# charge_battery.net
KiCad netlist of a schematic drawn in Altium Designer
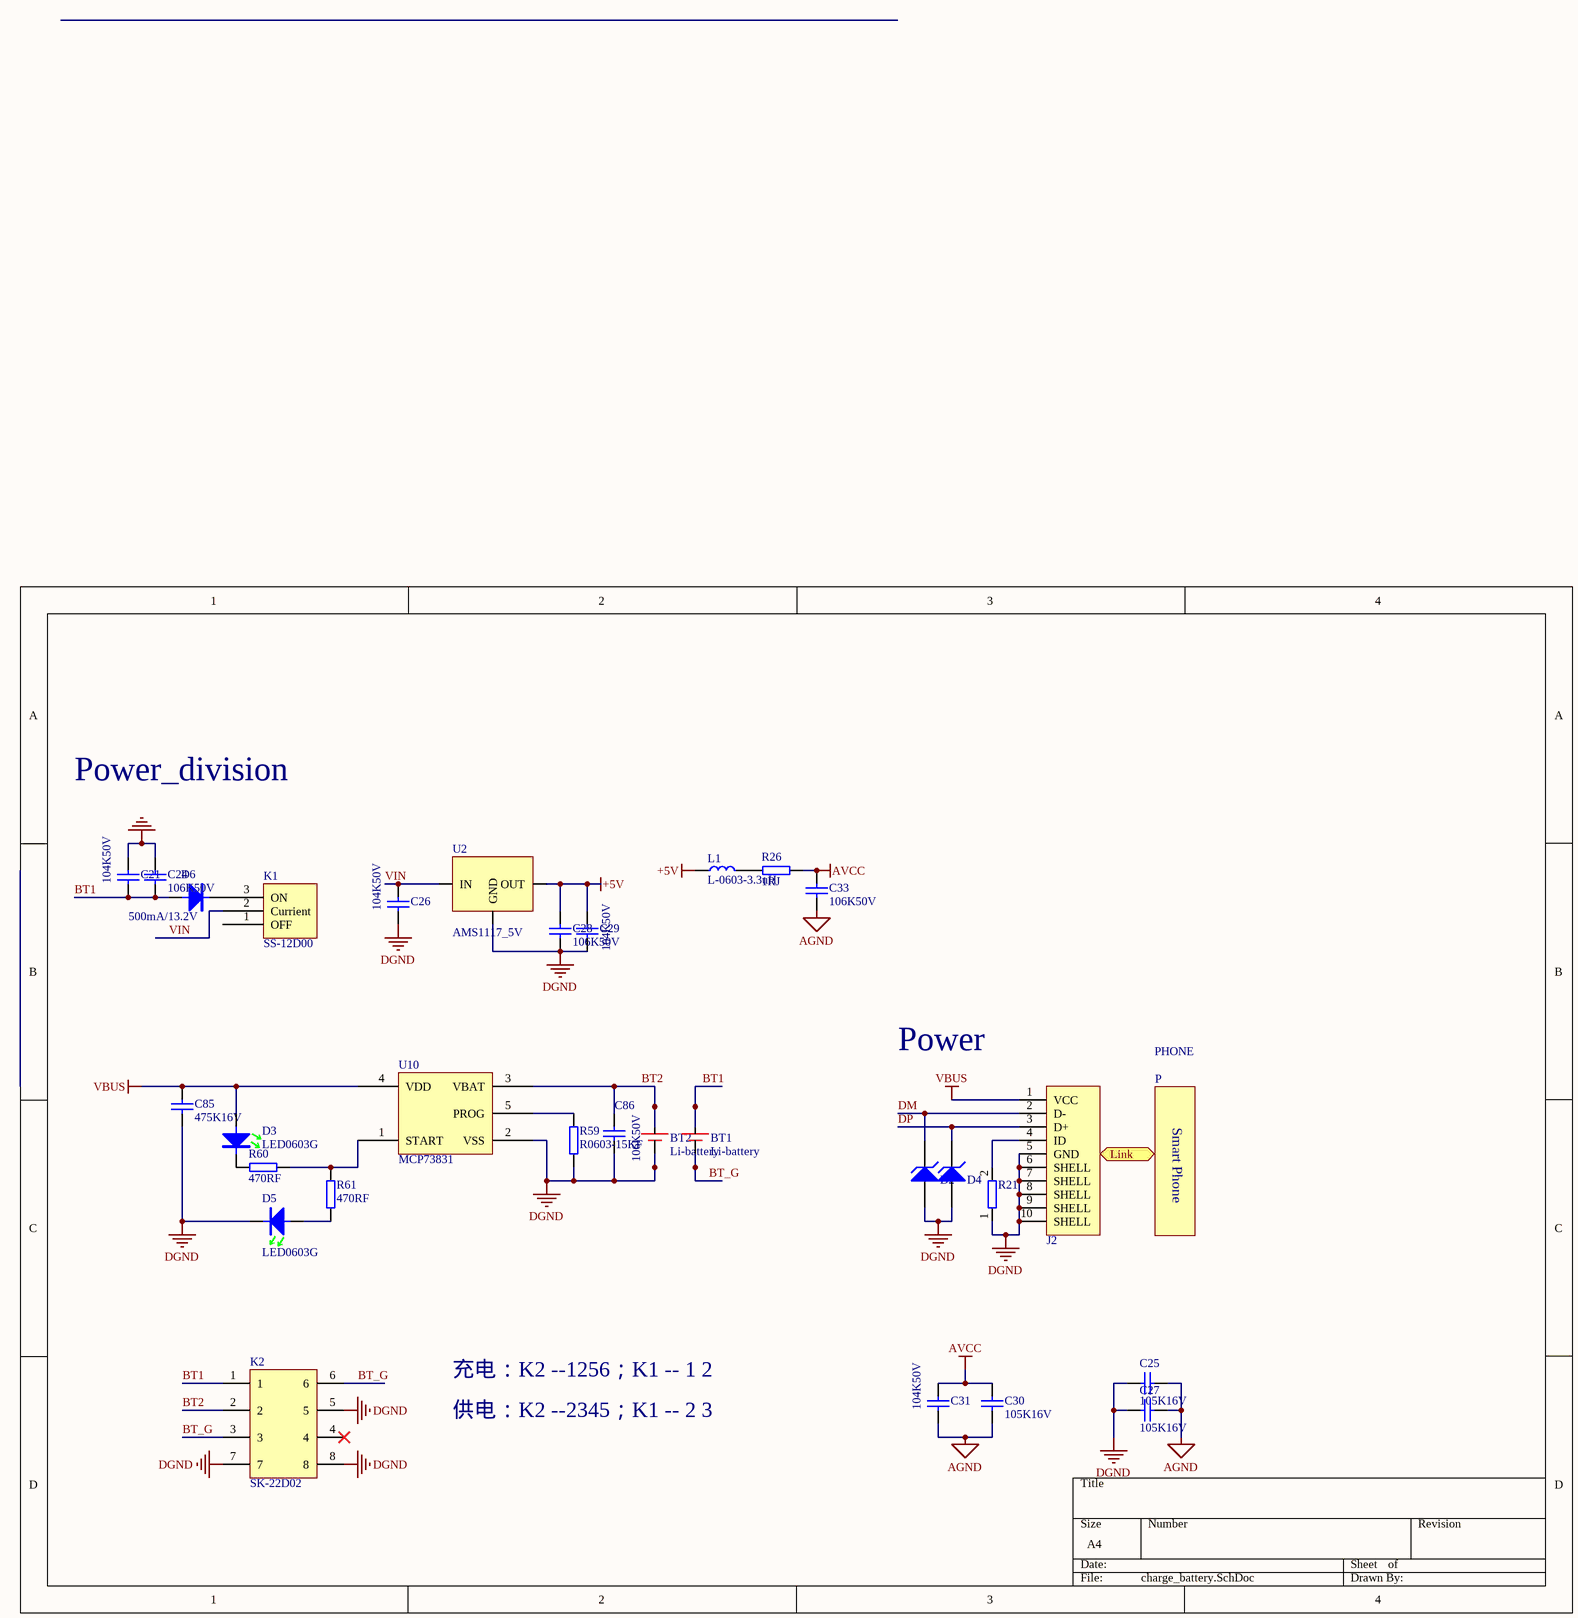
[diagram p0: charge_battery.SchDoc]

(export (version "E")
  (design (tool "Eeschema 10.0.6"))
  (components
    (comp (ref "BT1")
      (value "Li-battery")
      (footprint "LIR2032")
      (description "纽扣电池LIR2023")
      (libsource (lib "Others") (part "Li-batttery"))
    )
    (comp (ref "BT2")
      (value "Li-battery")
      (footprint "LIR2032")
      (description "纽扣电池LIR2023")
      (libsource (lib "Others") (part "Li-batttery"))
    )
    (comp (ref "C21")
      (value "104K50V")
      (footprint "C0603")
      (description "贴片电容-陶瓷")
      (libsource (lib "Capacitor") (part "C0603X7R-104K50V"))
    )
    (comp (ref "C24")
      (value "106K50V")
      (footprint "C0603")
      (description "贴片电容-陶瓷")
      (libsource (lib "Capacitor") (part "C0603X7R-106K50V"))
    )
    (comp (ref "C25")
      (value "105K16V")
      (footprint "C0603")
      (description "贴片电容-陶瓷")
      (libsource (lib "Capacitor") (part "C0603X7R-105K16V"))
    )
    (comp (ref "C26")
      (value "104K50V")
      (footprint "C0603")
      (description "贴片电容-陶瓷")
      (libsource (lib "Capacitor") (part "C0603X7R-104K50V"))
    )
    (comp (ref "C27")
      (value "105K16V")
      (footprint "C0603")
      (description "贴片电容-陶瓷")
      (libsource (lib "Capacitor") (part "C0603X7R-105K16V"))
    )
    (comp (ref "C28")
      (value "106K50V")
      (footprint "C0603")
      (description "贴片电容-陶瓷")
      (libsource (lib "Capacitor") (part "C0603X7R-106K50V"))
    )
    (comp (ref "C29")
      (value "104K50V")
      (footprint "C0603")
      (description "贴片电容-陶瓷")
      (libsource (lib "Capacitor") (part "C0603X7R-104K50V"))
    )
    (comp (ref "C30")
      (value "105K16V")
      (footprint "C0603")
      (description "贴片电容-陶瓷")
      (libsource (lib "Capacitor") (part "C0603X7R-105K16V"))
    )
    (comp (ref "C31")
      (value "104K50V")
      (footprint "C0603")
      (description "贴片电容-陶瓷")
      (libsource (lib "Capacitor") (part "C0603X7R-104K50V"))
    )
    (comp (ref "C33")
      (value "106K50V")
      (footprint "C0603")
      (description "贴片电容-陶瓷")
      (libsource (lib "Capacitor") (part "C0603X7R-106K50V"))
    )
    (comp (ref "C85")
      (value "475K16V")
      (footprint "C0603")
      (description "贴片电容-陶瓷")
      (libsource (lib "Capacitor") (part "C0603X7R-475K16V"))
    )
    (comp (ref "C86")
      (value "106K50V")
      (footprint "C0603")
      (description "贴片电容-陶瓷")
      (libsource (lib "Capacitor") (part "C0603X7R-106K50V"))
    )
    (comp (ref "D2")
      (value "ESDA_TR1/0603")
      (footprint "HS_0603D")
      (description "Zener Diode")
      (fields (field (name "PUBLISHER") "*"))
      (libsource (lib "aiwacV2.0") (part "D Zener"))
    )
    (comp (ref "D3")
      (value "LED0603G")
      (footprint "D-LED0603G")
      (description "贴片二极管-LED")
      (libsource (lib "Diode") (part "DLED-0603-G"))
    )
    (comp (ref "D4")
      (value "ESDA_TR1/0603")
      (footprint "HS_0603D")
      (description "Zener Diode")
      (fields (field (name "PUBLISHER") "*"))
      (libsource (lib "aiwacV2.0") (part "D Zener"))
    )
    (comp (ref "D5")
      (value "LED0603G")
      (footprint "D-LED0603G")
      (description "贴片二极管-LED")
      (libsource (lib "Diode") (part "DLED-0603-G"))
    )
    (comp (ref "D6")
      (value "500mA/13.2V")
      (footprint "D1206")
      (description "500mA/13.2V 自恢复保险丝")
      (libsource (lib "Diode") (part "1206MSD"))
    )
    (comp (ref "J2")
      (value "USB-MINI-SOCKET")
      (footprint "MICRO-USB - 5.9")
      (description "USB-A卧式插座")
      (libsource (lib "epic2") (part "J-USB-MINI-SOCKET"))
    )
    (comp (ref "K1")
      (value "SS-12D00")
      (footprint "SS-12D00")
      (libsource (lib "Key") (part "SS-12D00(1P2T) 立式 柄高5MM"))
    )
    (comp (ref "K2")
      (value "SK-22D02")
      (footprint "SK-22D02")
      (description "波动开关-2档6脚")
      (libsource (lib "Key") (part "SK-22D02"))
    )
    (comp (ref "L1")
      (value "L-0603-3.3uH")
      (footprint "L0603")
      (description "贴片电感-屏蔽")
      (libsource (lib "magnetic") (part "L-0603-3.3uH"))
    )
    (comp (ref "P") (value "PHONE") (libsource (lib "epic") (part "PHONE")))
    (comp (ref "R21")
      (value "0R")
      (footprint "R0603")
      (description "贴片电阻-通用")
      (libsource (lib "Resistor") (part "R0603-0R"))
    )
    (comp (ref "R26")
      (value "1RJ")
      (footprint "R0603")
      (description "贴片电阻-通用")
      (libsource (lib "Resistor") (part "R0603-1RJ"))
    )
    (comp (ref "R59")
      (value "R0603-15KF")
      (footprint "R0603")
      (description "贴片电容-通用")
      (libsource (lib "Resistor") (part "R0603-15KF"))
    )
    (comp (ref "R60")
      (value "470RF")
      (footprint "R0603")
      (description "贴片电阻-通用")
      (libsource (lib "Resistor") (part "R0603-470RF"))
    )
    (comp (ref "R61")
      (value "470RF")
      (footprint "R0603")
      (description "贴片电阻-通用")
      (libsource (lib "Resistor") (part "R0603-470RF"))
    )
    (comp (ref "U2") (value "AMS1117_5V") (footprint "SOT-223") (libsource (lib "IC") (part "AMS1117-5V")))
    (comp (ref "U10")
      (value "MCP73831")
      (footprint "SOT23-5N")
      (description "charge IC")
      (libsource (lib "IC") (part "MCP73831"))
    )
  )
  (nets
    (net (code "1") (name "+5V") (class "Default")
      (node (ref "C28") (pin "2") (pinfunction "2_2") (pintype "passive"))
      (node (ref "C29") (pin "1") (pinfunction "1_1") (pintype "passive"))
      (node (ref "L1") (pin "1") (pinfunction "1_1") (pintype "passive"))
      (node (ref "U2") (pin "2") (pinfunction "OUT_2") (pintype "passive"))
    )
    (net (code "2") (name "/BT1") (class "Default")
      (node (ref "BT1") (pin "1") (pinfunction "1_1") (pintype "passive"))
      (node (ref "C21") (pin "2") (pinfunction "2_2") (pintype "passive"))
      (node (ref "C24") (pin "1") (pinfunction "1_1") (pintype "passive"))
      (node (ref "D6") (pin "1") (pinfunction "1_1") (pintype "passive"))
      (node (ref "K2") (pin "1") (pinfunction "1_1") (pintype "passive"))
    )
    (net (code "3") (name "/BT2") (class "Default")
      (node (ref "BT2") (pin "1") (pinfunction "1_1") (pintype "passive"))
      (node (ref "C86") (pin "1") (pinfunction "1_1") (pintype "passive"))
      (node (ref "K2") (pin "2") (pinfunction "2_2") (pintype "passive"))
      (node (ref "U10") (pin "3") (pinfunction "VBAT_3") (pintype "passive"))
    )
    (net (code "4") (name "/BT_G") (class "Default")
      (node (ref "BT1") (pin "2") (pinfunction "2_2") (pintype "passive"))
      (node (ref "K2") (pin "3") (pinfunction "3_3") (pintype "passive"))
      (node (ref "K2") (pin "6") (pinfunction "6_6") (pintype "passive"))
    )
    (net (code "5") (name "/DM") (class "Default")
      (node (ref "D2") (pin "2") (pinfunction "K_2") (pintype "passive"))
      (node (ref "J2") (pin "2") (pinfunction "D-_2") (pintype "passive"))
    )
    (net (code "6") (name "/DP") (class "Default")
      (node (ref "D4") (pin "2") (pinfunction "K_2") (pintype "passive"))
      (node (ref "J2") (pin "3") (pinfunction "D+_3") (pintype "passive"))
    )
    (net (code "8") (name "/VIN") (class "Default")
      (node (ref "C26") (pin "1") (pinfunction "1_1") (pintype "passive"))
      (node (ref "K1") (pin "2") (pinfunction "Currient_2") (pintype "passive"))
      (node (ref "U2") (pin "3") (pinfunction "IN_3") (pintype "passive"))
    )
    (net (code "9") (name "AGND") (class "Default")
      (node (ref "C25") (pin "2") (pinfunction "2_2") (pintype "passive"))
      (node (ref "C27") (pin "2") (pinfunction "2_2") (pintype "passive"))
      (node (ref "C30") (pin "2") (pinfunction "2_2") (pintype "passive"))
      (node (ref "C31") (pin "2") (pinfunction "2_2") (pintype "passive"))
      (node (ref "C33") (pin "1") (pinfunction "1_1") (pintype "passive"))
    )
    (net (code "10") (name "AVCC") (class "Default")
      (node (ref "C30") (pin "1") (pinfunction "1_1") (pintype "passive"))
      (node (ref "C31") (pin "1") (pinfunction "1_1") (pintype "passive"))
      (node (ref "C33") (pin "2") (pinfunction "2_2") (pintype "passive"))
      (node (ref "R26") (pin "1") (pinfunction "1_1") (pintype "passive"))
    )
    (net (code "11") (name "DGND") (class "Default")
      (node (ref "BT2") (pin "2") (pinfunction "2_2") (pintype "passive"))
      (node (ref "C21") (pin "1") (pinfunction "1_1") (pintype "passive"))
      (node (ref "C24") (pin "2") (pinfunction "2_2") (pintype "passive"))
      (node (ref "C25") (pin "1") (pinfunction "1_1") (pintype "passive"))
      (node (ref "C26") (pin "2") (pinfunction "2_2") (pintype "passive"))
      (node (ref "C27") (pin "1") (pinfunction "1_1") (pintype "passive"))
      (node (ref "C28") (pin "1") (pinfunction "1_1") (pintype "passive"))
      (node (ref "C29") (pin "2") (pinfunction "2_2") (pintype "passive"))
      (node (ref "C85") (pin "2") (pinfunction "2_2") (pintype "passive"))
      (node (ref "C86") (pin "2") (pinfunction "2_2") (pintype "passive"))
      (node (ref "D2") (pin "1") (pinfunction "A_1") (pintype "passive"))
      (node (ref "D4") (pin "1") (pinfunction "A_1") (pintype "passive"))
      (node (ref "D5") (pin "2") (pinfunction "2_2") (pintype "passive"))
      (node (ref "J2") (pin "10") (pinfunction "SHELL_10") (pintype "passive"))
      (node (ref "J2") (pin "5") (pinfunction "GND_5") (pintype "passive"))
      (node (ref "J2") (pin "6") (pinfunction "SHELL_6") (pintype "passive"))
      (node (ref "J2") (pin "7") (pinfunction "SHELL_7") (pintype "passive"))
      (node (ref "J2") (pin "8") (pinfunction "SHELL_8") (pintype "passive"))
      (node (ref "J2") (pin "9") (pinfunction "SHELL_9") (pintype "passive"))
      (node (ref "K2") (pin "5") (pinfunction "5_5") (pintype "passive"))
      (node (ref "K2") (pin "7") (pinfunction "7_7") (pintype "passive"))
      (node (ref "K2") (pin "8") (pinfunction "8_8") (pintype "passive"))
      (node (ref "R21") (pin "1") (pinfunction "1_1") (pintype "passive"))
      (node (ref "R59") (pin "1") (pinfunction "1_1") (pintype "passive"))
      (node (ref "U10") (pin "2") (pinfunction "VSS_2") (pintype "passive"))
      (node (ref "U2") (pin "1") (pinfunction "GND_1") (pintype "passive"))
    )
    (net (code "12") (name "Net-(D3-Pad2)") (class "Default")
      (node (ref "D3") (pin "2") (pinfunction "2_2") (pintype "passive"))
      (node (ref "R60") (pin "1") (pinfunction "1_1") (pintype "passive"))
    )
    (net (code "13") (name "Net-(D5-Pad1)") (class "Default")
      (node (ref "D5") (pin "1") (pinfunction "1_1") (pintype "passive"))
      (node (ref "R61") (pin "1") (pinfunction "1_1") (pintype "passive"))
    )
    (net (code "14") (name "Net-(J2-ID)") (class "Default")
      (node (ref "J2") (pin "4") (pinfunction "ID_4") (pintype "passive"))
      (node (ref "R21") (pin "2") (pinfunction "2_2") (pintype "passive"))
    )
    (net (code "15") (name "Net-(K1-ON)") (class "Default")
      (node (ref "D6") (pin "2") (pinfunction "2_2") (pintype "passive"))
      (node (ref "K1") (pin "3") (pinfunction "ON_3") (pintype "passive"))
    )
    (net (code "16") (name "Net-(L1-Pad2)") (class "Default")
      (node (ref "L1") (pin "2") (pinfunction "2_2") (pintype "passive"))
      (node (ref "R26") (pin "2") (pinfunction "2_2") (pintype "passive"))
    )
    (net (code "17") (name "Net-(U10-PROG)") (class "Default")
      (node (ref "R59") (pin "2") (pinfunction "2_2") (pintype "passive"))
      (node (ref "U10") (pin "5") (pinfunction "PROG_5") (pintype "passive"))
    )
    (net (code "18") (name "Net-(U10-START)") (class "Default")
      (node (ref "R60") (pin "2") (pinfunction "2_2") (pintype "passive"))
      (node (ref "R61") (pin "2") (pinfunction "2_2") (pintype "passive"))
      (node (ref "U10") (pin "1") (pinfunction "START_1") (pintype "passive"))
    )
    (net (code "19") (name "VBUS") (class "Default")
      (node (ref "C85") (pin "1") (pinfunction "1_1") (pintype "passive"))
      (node (ref "D3") (pin "1") (pinfunction "1_1") (pintype "passive"))
      (node (ref "J2") (pin "1") (pinfunction "VCC_1") (pintype "passive"))
      (node (ref "U10") (pin "4") (pinfunction "VDD_4") (pintype "passive"))
    )
    (net (code "20") (name "unconnected-(K1-OFF-Pad1)") (class "Default")
      (node (ref "K1") (pin "1") (pinfunction "OFF_1") (pintype "passive"))
    )
    (net (code "21") (name "unconnected-(K2-Pad4)") (class "Default")
      (node (ref "K2") (pin "4") (pinfunction "4_4") (pintype "passive+no_connect"))
    )
  )
)
